# design.net
KiCad netlist of a schematic drawn in Altium Designer
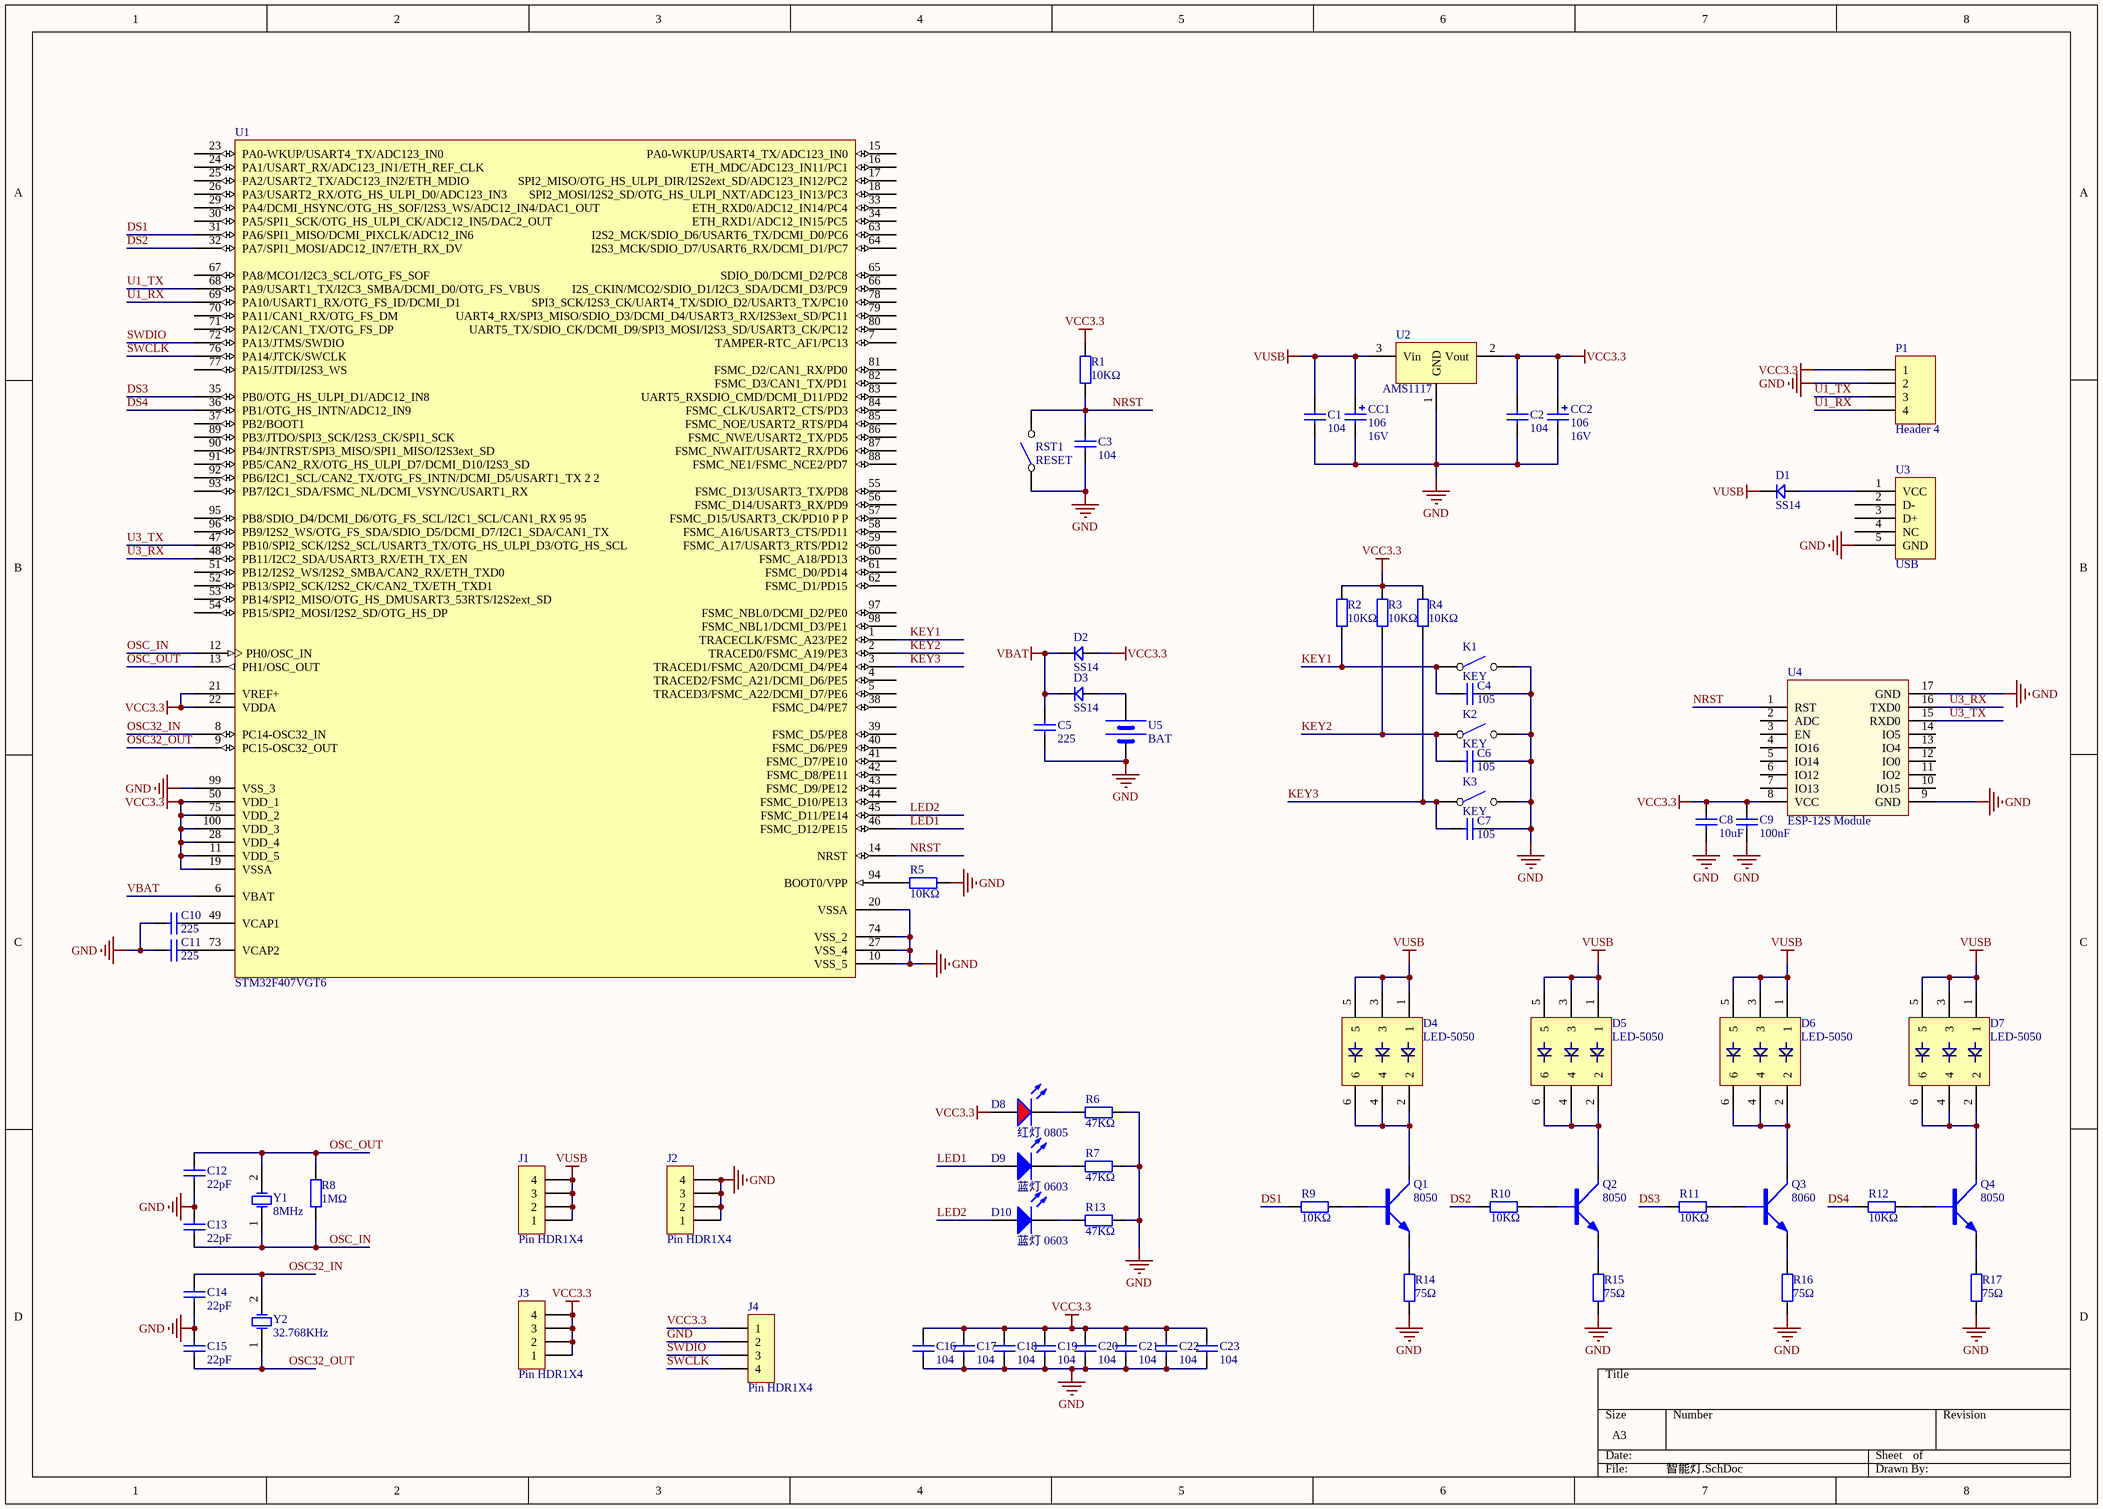
[diagram p0: 智能灯.SchDoc]

(export (version "E")
  (design (tool "Eeschema 10.0.6"))
  (components
    (comp (ref "C1")
      (value "104")
      (footprint "LC-0805_C")
      (description "贴片电容")
      (libsource (lib "Miscellaneous Devices LC") (part "0805 6.8nF (682) 10% 50V"))
    )
    (comp (ref "C2")
      (value "104")
      (footprint "LC-0805_C")
      (description "贴片电容")
      (libsource (lib "Miscellaneous Devices LC") (part "0805 6.8nF (682) 10% 50V"))
    )
    (comp (ref "C3")
      (value "104")
      (footprint "LC-0805_C")
      (description "贴片电容")
      (libsource (lib "Miscellaneous Devices LC") (part "0805 330nF (334) 10% 50V"))
    )
    (comp (ref "C4")
      (value "105")
      (footprint "LC-0805_C")
      (description "贴片电容")
      (libsource (lib "Miscellaneous Devices LC") (part "0805 6.8nF (682) 10% 50V"))
    )
    (comp (ref "C5")
      (value "225")
      (footprint "LC-0805_C")
      (description "贴片电容")
      (libsource (lib "Miscellaneous Devices LC") (part "0805 6.8nF (682) 10% 50V"))
    )
    (comp (ref "C6")
      (value "105")
      (footprint "LC-0805_C")
      (description "贴片电容")
      (libsource (lib "Miscellaneous Devices LC") (part "0805 6.8nF (682) 10% 50V"))
    )
    (comp (ref "C7")
      (value "105")
      (footprint "LC-0805_C")
      (description "贴片电容")
      (libsource (lib "Miscellaneous Devices LC") (part "0805 6.8nF (682) 10% 50V"))
    )
    (comp (ref "C8")
      (value "10uF")
      (footprint "LC-0805_C")
      (description "贴片电容")
      (libsource (lib "Miscellaneous Devices LC") (part "0805 6.8nF (682) 10% 50V"))
    )
    (comp (ref "C9")
      (value "100nF")
      (footprint "LC-0805_C")
      (description "贴片电容")
      (libsource (lib "Miscellaneous Devices LC") (part "0805 6.8nF (682) 10% 50V"))
    )
    (comp (ref "C10")
      (value "225")
      (footprint "LC-0805_C")
      (description "贴片电容")
      (libsource (lib "Miscellaneous Devices LC") (part "0805 6.8nF (682) 10% 50V"))
    )
    (comp (ref "C11")
      (value "225")
      (footprint "LC-0805_C")
      (description "贴片电容")
      (libsource (lib "Miscellaneous Devices LC") (part "0805 6.8nF (682) 10% 50V"))
    )
    (comp (ref "C12")
      (value "22pF")
      (footprint "LC-0805_C")
      (description "贴片电容")
      (libsource (lib "Miscellaneous Devices LC") (part "0805 6pF (6R0) 0.25pF 50V"))
    )
    (comp (ref "C13")
      (value "22pF")
      (footprint "LC-0805_C")
      (description "贴片电容")
      (libsource (lib "Miscellaneous Devices LC") (part "0805 6pF (6R0) 0.25pF 50V"))
    )
    (comp (ref "C14")
      (value "22pF")
      (footprint "LC-0805_C")
      (description "贴片电容")
      (libsource (lib "Miscellaneous Devices LC") (part "0805 6pF (6R0) 0.25pF 50V"))
    )
    (comp (ref "C15")
      (value "22pF")
      (footprint "LC-0805_C")
      (description "贴片电容")
      (libsource (lib "Miscellaneous Devices LC") (part "0805 6pF (6R0) 0.25pF 50V"))
    )
    (comp (ref "C16")
      (value "104")
      (footprint "LC-0805_C")
      (description "贴片电容")
      (libsource (lib "Miscellaneous Devices LC") (part "0805 6.8nF (682) 10% 50V"))
    )
    (comp (ref "C17")
      (value "104")
      (footprint "LC-0805_C")
      (description "贴片电容")
      (libsource (lib "Miscellaneous Devices LC") (part "0805 6.8nF (682) 10% 50V"))
    )
    (comp (ref "C18")
      (value "104")
      (footprint "LC-0805_C")
      (description "贴片电容")
      (libsource (lib "Miscellaneous Devices LC") (part "0805 6.8nF (682) 10% 50V"))
    )
    (comp (ref "C19")
      (value "104")
      (footprint "LC-0805_C")
      (description "贴片电容")
      (libsource (lib "Miscellaneous Devices LC") (part "0805 6.8nF (682) 10% 50V"))
    )
    (comp (ref "C20")
      (value "104")
      (footprint "LC-0805_C")
      (description "贴片电容")
      (libsource (lib "Miscellaneous Devices LC") (part "0805 6.8nF (682) 10% 50V"))
    )
    (comp (ref "C21")
      (value "104")
      (footprint "LC-0805_C")
      (description "贴片电容")
      (libsource (lib "Miscellaneous Devices LC") (part "0805 6.8nF (682) 10% 50V"))
    )
    (comp (ref "C22")
      (value "104")
      (footprint "LC-0805_C")
      (description "贴片电容")
      (libsource (lib "Miscellaneous Devices LC") (part "0805 6.8nF (682) 10% 50V"))
    )
    (comp (ref "C23")
      (value "104")
      (footprint "LC-0805_C")
      (description "贴片电容")
      (libsource (lib "Miscellaneous Devices LC") (part "0805 6.8nF (682) 10% 50V"))
    )
    (comp (ref "CC1")
      (value "Cap Tan C")
      (footprint "TAN-C-6032")
      (description "Polarized Capacitor (Radial)")
      (fields
        (field (name "CAPACITANCE") "106")
        (field (name "VOLTAGE") "16V")
        (field (name "PUBLISHER") "Altium Limited")
      )
      (libsource (lib "MyLib") (part "Cap Tan C"))
    )
    (comp (ref "CC2")
      (value "Cap Tan C")
      (footprint "TAN-C-6032")
      (description "Polarized Capacitor (Radial)")
      (fields
        (field (name "CAPACITANCE") "106")
        (field (name "VOLTAGE") "16V")
        (field (name "PUBLISHER") "Altium Limited")
      )
      (libsource (lib "MyLib") (part "Cap Tan C"))
    )
    (comp (ref "D1")
      (value "SS14")
      (footprint "Miscellaneous Devices LC:LC-SOD-123")
      (libsource (lib "Explorer STM32F407封装库") (part "D"))
    )
    (comp (ref "D2")
      (value "SS14")
      (footprint "Miscellaneous Devices LC:LC-SOD-123")
      (libsource (lib "Explorer STM32F407封装库") (part "D"))
    )
    (comp (ref "D3")
      (value "SS14")
      (footprint "Miscellaneous Devices LC:LC-SOD-123")
      (libsource (lib "Explorer STM32F407封装库") (part "D"))
    )
    (comp (ref "D4") (value "LED-5050") (footprint "LED-5050W") (libsource (lib "LED") (part "LED-5050")))
    (comp (ref "D5") (value "LED-5050") (footprint "LED-5050W") (libsource (lib "LED") (part "LED-5050")))
    (comp (ref "D6") (value "LED-5050") (footprint "LED-5050W") (libsource (lib "LED") (part "LED-5050")))
    (comp (ref "D7") (value "LED-5050") (footprint "LED-5050W") (libsource (lib "LED") (part "LED-5050")))
    (comp (ref "D8")
      (value "红灯 0805")
      (footprint "LC-0805_LED_S1")
      (description "发光二极管")
      (libsource (lib "Miscellaneous Devices LC") (part "0805 红灯"))
    )
    (comp (ref "D9")
      (value "蓝灯 0603")
      (footprint "Miscellaneous Devices LC:LC-0805_LED_S1")
      (description "发光二极管")
      (libsource (lib "Miscellaneous Devices LC") (part "0603 蓝灯"))
    )
    (comp (ref "D10")
      (value "蓝灯 0603")
      (footprint "Miscellaneous Devices LC:LC-0805_LED_S1")
      (description "发光二极管")
      (libsource (lib "Miscellaneous Devices LC") (part "0603 蓝灯"))
    )
    (comp (ref "J1")
      (value "Pin HDR1X4")
      (footprint "Pin HDR1X4/2.54mm-S")
      (libsource (lib "排针") (part "Pin HDR1X4"))
    )
    (comp (ref "J2")
      (value "Pin HDR1X4")
      (footprint "Pin HDR1X4/2.54mm-S")
      (libsource (lib "排针") (part "Pin HDR1X4"))
    )
    (comp (ref "J3")
      (value "Pin HDR1X4")
      (footprint "Pin HDR1X4/2.54mm-S")
      (libsource (lib "排针") (part "Pin HDR1X4"))
    )
    (comp (ref "J4")
      (value "Pin HDR1X4")
      (footprint "Pin HDR1X4/2.54mm-S")
      (libsource (lib "") (part "Pin HDR1X4_1"))
    )
    (comp (ref "K1")
      (value "KEY")
      (footprint "MyLib:KEY_2")
      (description "微动开关")
      (libsource (lib "MyLib") (part "KEY"))
    )
    (comp (ref "K2")
      (value "KEY")
      (footprint "MyLib:KEY_2")
      (description "微动开关")
      (libsource (lib "MyLib") (part "KEY"))
    )
    (comp (ref "K3")
      (value "KEY")
      (footprint "MyLib:KEY_2")
      (description "微动开关")
      (libsource (lib "MyLib") (part "KEY"))
    )
    (comp (ref "P1")
      (value "Header 4")
      (footprint "MyLib:HDR1X4")
      (description "Header, 4-Pin")
      (fields (field (name "PUBLISHER") "Altium Limited"))
      (libsource (lib "MyLib") (part "Header 4"))
    )
    (comp (ref "Q1")
      (value "8050")
      (footprint "SOT-23")
      (description "NPN三极管")
      (libsource (lib "三极管") (part "NPN"))
    )
    (comp (ref "Q2")
      (value "8050")
      (footprint "SOT-23")
      (description "NPN三极管")
      (libsource (lib "三极管") (part "NPN"))
    )
    (comp (ref "Q3")
      (value "8060")
      (footprint "SOT-23")
      (description "NPN三极管")
      (libsource (lib "三极管") (part "NPN"))
    )
    (comp (ref "Q4")
      (value "8050")
      (footprint "SOT-23")
      (description "NPN三极管")
      (libsource (lib "三极管") (part "NPN"))
    )
    (comp (ref "R1")
      (value "10KΩ")
      (footprint "LC-0805_R")
      (description "贴片电阻")
      (libsource (lib "Miscellaneous Devices LC") (part "0805 390KΩ (3903) 1%"))
    )
    (comp (ref "R2")
      (value "10KΩ")
      (footprint "LC-0805_R")
      (description "贴片电阻")
      (libsource (lib "") (part "0805 11KΩ (1102) 1%_1"))
    )
    (comp (ref "R3")
      (value "10KΩ")
      (footprint "LC-0805_R")
      (description "贴片电阻")
      (libsource (lib "") (part "0805 11KΩ (1102) 1%_1"))
    )
    (comp (ref "R4")
      (value "10KΩ")
      (footprint "LC-0805_R")
      (description "贴片电阻")
      (libsource (lib "") (part "0805 11KΩ (1102) 1%_1"))
    )
    (comp (ref "R5")
      (value "10KΩ")
      (footprint "LC-0805_R")
      (description "贴片电阻")
      (libsource (lib "Miscellaneous Devices LC") (part "0805 1.8KΩ (1801) 1%"))
    )
    (comp (ref "R6")
      (value "47KΩ")
      (footprint "LC-0805_R")
      (description "贴片电阻")
      (libsource (lib "Miscellaneous Devices LC") (part "0805 11KΩ (1102) 1%"))
    )
    (comp (ref "R7")
      (value "47KΩ")
      (footprint "LC-0805_R")
      (description "贴片电阻")
      (libsource (lib "Miscellaneous Devices LC") (part "0805 11KΩ (1102) 1%"))
    )
    (comp (ref "R8")
      (value "1MΩ")
      (footprint "LC-0805_R")
      (description "贴片电阻")
      (libsource (lib "Miscellaneous Devices LC") (part "0805 390KΩ (3903) 1%"))
    )
    (comp (ref "R9")
      (value "10KΩ")
      (footprint "LC-0805_R")
      (description "贴片电阻")
      (libsource (lib "") (part "0805 11KΩ (1102) 1%_2"))
    )
    (comp (ref "R10")
      (value "10KΩ")
      (footprint "电阻:0805R")
      (description "贴片电阻")
      (libsource (lib "") (part "0805 11KΩ (1102) 1%_2"))
    )
    (comp (ref "R11")
      (value "10KΩ")
      (footprint "电阻:0805R")
      (description "贴片电阻")
      (libsource (lib "") (part "0805 11KΩ (1102) 1%_2"))
    )
    (comp (ref "R12")
      (value "10KΩ")
      (footprint "电阻:0805R")
      (description "贴片电阻")
      (libsource (lib "") (part "0805 11KΩ (1102) 1%_2"))
    )
    (comp (ref "R13")
      (value "47KΩ")
      (footprint "LC-0805_R")
      (description "贴片电阻")
      (libsource (lib "Miscellaneous Devices LC") (part "0805 11KΩ (1102) 1%"))
    )
    (comp (ref "R14")
      (value "75Ω")
      (footprint "电阻:0805R")
      (description "贴片电阻")
      (libsource (lib "Miscellaneous Devices LC") (part "0805 1.2KΩ (1201) 1%"))
    )
    (comp (ref "R15")
      (value "75Ω")
      (footprint "电阻:0805R")
      (description "贴片电阻")
      (libsource (lib "Miscellaneous Devices LC") (part "0805 1.2KΩ (1201) 1%"))
    )
    (comp (ref "R16")
      (value "75Ω")
      (footprint "电阻:0805R")
      (description "贴片电阻")
      (libsource (lib "Miscellaneous Devices LC") (part "0805 1.2KΩ (1201) 1%"))
    )
    (comp (ref "R17")
      (value "75Ω")
      (footprint "电阻:0805R")
      (description "贴片电阻")
      (libsource (lib "Miscellaneous Devices LC") (part "0805 1.2KΩ (1201) 1%"))
    )
    (comp (ref "RST1")
      (value "RESET")
      (footprint "MyLib:KEY_2")
      (description "微动开关")
      (libsource (lib "MyLib") (part "KEY"))
    )
    (comp (ref "U1")
      (value "STM32F407VGT6")
      (footprint "STM32系列:LQFP100 14x14")
      (libsource (lib "STM32F407系列") (part "STM32F407VGT6"))
    )
    (comp (ref "U2")
      (value "AMS1117")
      (footprint "MyLib:SOT-223")
      (description "3.3V电压转换器AMS1117")
      (libsource (lib "My Footprint") (part "AMS1117"))
    )
    (comp (ref "U3") (value "USB") (footprint "MyLib:USB_B") (libsource (lib "MyLib") (part "USB")))
    (comp (ref "U4")
      (value "ESP-12S Module")
      (footprint "ESP-12S Module")
      (libsource (lib "MyLib") (part "ESP-12S Module"))
    )
    (comp (ref "U5")
      (value "BAT")
      (footprint "MyLib:CR1220_A")
      (description "纽扣电池座CR1220")
      (libsource (lib "MyLib") (part "BAT"))
    )
    (comp (ref "Y1")
      (value "8MHz")
      (footprint "MyLib:XTAL-SMD")
      (description "晶体振荡器")
      (fields (field (name "PUBLISHER") "Altium Limited"))
      (libsource (lib "MyLib") (part "XTAL"))
    )
    (comp (ref "Y2")
      (value "32.768KHz")
      (footprint "晶振:OSC-3x8-WI-B")
      (description "晶体振荡器")
      (fields (field (name "PUBLISHER") "Altium Limited"))
      (libsource (lib "MyLib") (part "XTAL"))
    )
  )
  (nets
    (net (code "1") (name "/DS1") (class "Default")
      (node (ref "R9") (pin "2") (pinfunction "2_2") (pintype "passive"))
      (node (ref "U1") (pin "31") (pinfunction "PA6/SPI1_MISO/DCMI_PIXCLK/ADC12_IN6_31") (pintype "bidirectional"))
    )
    (net (code "2") (name "/DS2") (class "Default")
      (node (ref "R10") (pin "2") (pinfunction "2_2") (pintype "passive"))
      (node (ref "U1") (pin "32") (pinfunction "PA7/SPI1_MOSI/ADC12_IN7/ETH_RX_DV_32") (pintype "bidirectional"))
    )
    (net (code "3") (name "/DS3") (class "Default")
      (node (ref "R11") (pin "2") (pinfunction "2_2") (pintype "passive"))
      (node (ref "U1") (pin "35") (pinfunction "PB0/OTG_HS_ULPI_D1/ADC12_IN8_35") (pintype "bidirectional"))
    )
    (net (code "4") (name "/DS4") (class "Default")
      (node (ref "R12") (pin "2") (pinfunction "2_2") (pintype "passive"))
      (node (ref "U1") (pin "36") (pinfunction "PB1/OTG_HS_INTN/ADC12_IN9_36") (pintype "bidirectional"))
    )
    (net (code "5") (name "/KEY1") (class "Default")
      (node (ref "C4") (pin "1") (pinfunction "1_1") (pintype "passive"))
      (node (ref "K1") (pin "1") (pinfunction "1_1") (pintype "passive"))
      (node (ref "R2") (pin "1") (pinfunction "1_1") (pintype "passive"))
      (node (ref "U1") (pin "1") (pinfunction "TRACECLK/FSMC_A23/PE2_1") (pintype "bidirectional"))
    )
    (net (code "6") (name "/KEY2") (class "Default")
      (node (ref "C6") (pin "1") (pinfunction "1_1") (pintype "passive"))
      (node (ref "K2") (pin "1") (pinfunction "1_1") (pintype "passive"))
      (node (ref "R3") (pin "1") (pinfunction "1_1") (pintype "passive"))
      (node (ref "U1") (pin "2") (pinfunction "TRACED0/FSMC_A19/PE3_2") (pintype "bidirectional"))
    )
    (net (code "7") (name "/KEY3") (class "Default")
      (node (ref "C7") (pin "1") (pinfunction "1_1") (pintype "passive"))
      (node (ref "K3") (pin "1") (pinfunction "1_1") (pintype "passive"))
      (node (ref "R4") (pin "1") (pinfunction "1_1") (pintype "passive"))
      (node (ref "U1") (pin "3") (pinfunction "TRACED1/FSMC_A20/DCMI_D4/PE4_3") (pintype "bidirectional"))
    )
    (net (code "8") (name "/LED1") (class "Default")
      (node (ref "D9") (pin "A") (pinfunction "A_A") (pintype "passive"))
      (node (ref "U1") (pin "46") (pinfunction "FSMC_D12/PE15_46") (pintype "bidirectional"))
    )
    (net (code "9") (name "/LED2") (class "Default")
      (node (ref "D10") (pin "A") (pinfunction "A_A") (pintype "passive"))
      (node (ref "U1") (pin "45") (pinfunction "FSMC_D11/PE14_45") (pintype "bidirectional"))
    )
    (net (code "10") (name "/NRST") (class "Default")
      (node (ref "C3") (pin "2") (pinfunction "2_2") (pintype "passive"))
      (node (ref "R1") (pin "1") (pinfunction "1_1") (pintype "passive"))
      (node (ref "RST1") (pin "2") (pinfunction "2_2") (pintype "passive"))
      (node (ref "U1") (pin "14") (pinfunction "NRST_14") (pintype "bidirectional"))
      (node (ref "U4") (pin "1") (pinfunction "RST_1") (pintype "passive"))
    )
    (net (code "11") (name "/OSC32_IN") (class "Default")
      (node (ref "C14") (pin "2") (pinfunction "2_2") (pintype "passive"))
      (node (ref "U1") (pin "8") (pinfunction "PC14-OSC32_IN_8") (pintype "bidirectional"))
      (node (ref "Y2") (pin "2") (pinfunction "OSC2_2") (pintype "passive"))
    )
    (net (code "12") (name "/OSC32_OUT") (class "Default")
      (node (ref "C15") (pin "1") (pinfunction "1_1") (pintype "passive"))
      (node (ref "U1") (pin "9") (pinfunction "PC15-OSC32_OUT_9") (pintype "bidirectional"))
      (node (ref "Y2") (pin "1") (pinfunction "OSC1_1") (pintype "passive"))
    )
    (net (code "13") (name "/OSC_IN") (class "Default")
      (node (ref "C13") (pin "1") (pinfunction "1_1") (pintype "passive"))
      (node (ref "R8") (pin "1") (pinfunction "1_1") (pintype "passive"))
      (node (ref "U1") (pin "12") (pinfunction "PH0/OSC_IN_12") (pintype "input"))
      (node (ref "Y1") (pin "1") (pinfunction "OSC1_1") (pintype "passive"))
    )
    (net (code "14") (name "/OSC_OUT") (class "Default")
      (node (ref "C12") (pin "2") (pinfunction "2_2") (pintype "passive"))
      (node (ref "R8") (pin "2") (pinfunction "2_2") (pintype "passive"))
      (node (ref "U1") (pin "13") (pinfunction "PH1/OSC_OUT_13") (pintype "output"))
      (node (ref "Y1") (pin "2") (pinfunction "OSC2_2") (pintype "passive"))
    )
    (net (code "15") (name "/SWCLK") (class "Default")
      (node (ref "J4") (pin "4") (pinfunction "4_4") (pintype "passive"))
      (node (ref "U1") (pin "76") (pinfunction "PA14/JTCK/SWCLK_76") (pintype "bidirectional"))
    )
    (net (code "16") (name "/SWDIO") (class "Default")
      (node (ref "J4") (pin "3") (pinfunction "3_3") (pintype "passive"))
      (node (ref "U1") (pin "72") (pinfunction "PA13/JTMS/SWDIO_72") (pintype "bidirectional"))
    )
    (net (code "17") (name "/U1_RX") (class "Default")
      (node (ref "P1") (pin "4") (pinfunction "4_4") (pintype "passive"))
      (node (ref "U1") (pin "69") (pinfunction "PA10/USART1_RX/OTG_FS_ID/DCMI_D1_69") (pintype "bidirectional"))
    )
    (net (code "18") (name "/U1_TX") (class "Default")
      (node (ref "P1") (pin "3") (pinfunction "3_3") (pintype "passive"))
      (node (ref "U1") (pin "68") (pinfunction "PA9/USART1_TX/I2C3_SMBA/DCMI_D0/OTG_FS_VBUS_68") (pintype "bidirectional"))
    )
    (net (code "19") (name "/U3_RX") (class "Default")
      (node (ref "U1") (pin "48") (pinfunction "PB11/I2C2_SDA/USART3_RX/ETH_TX_EN_48") (pintype "bidirectional"))
      (node (ref "U4") (pin "16") (pinfunction "TXD0_16") (pintype "passive"))
    )
    (net (code "20") (name "/U3_TX") (class "Default")
      (node (ref "U1") (pin "47") (pinfunction "PB10/SPI2_SCK/I2S2_SCL/USART3_TX/OTG_HS_ULPI_D3/OTG_HS_SCL_47") (pintype "bidirectional"))
      (node (ref "U4") (pin "15") (pinfunction "RXD0_15") (pintype "passive"))
    )
    (net (code "21") (name "GND") (class "Default")
      (node (ref "C1") (pin "1") (pinfunction "1_1") (pintype "passive"))
      (node (ref "C10") (pin "1") (pinfunction "1_1") (pintype "passive"))
      (node (ref "C11") (pin "1") (pinfunction "1_1") (pintype "passive"))
      (node (ref "C12") (pin "1") (pinfunction "1_1") (pintype "passive"))
      (node (ref "C13") (pin "2") (pinfunction "2_2") (pintype "passive"))
      (node (ref "C14") (pin "1") (pinfunction "1_1") (pintype "passive"))
      (node (ref "C15") (pin "2") (pinfunction "2_2") (pintype "passive"))
      (node (ref "C16") (pin "1") (pinfunction "1_1") (pintype "passive"))
      (node (ref "C17") (pin "1") (pinfunction "1_1") (pintype "passive"))
      (node (ref "C18") (pin "1") (pinfunction "1_1") (pintype "passive"))
      (node (ref "C19") (pin "1") (pinfunction "1_1") (pintype "passive"))
      (node (ref "C2") (pin "1") (pinfunction "1_1") (pintype "passive"))
      (node (ref "C20") (pin "1") (pinfunction "1_1") (pintype "passive"))
      (node (ref "C21") (pin "1") (pinfunction "1_1") (pintype "passive"))
      (node (ref "C22") (pin "1") (pinfunction "1_1") (pintype "passive"))
      (node (ref "C23") (pin "1") (pinfunction "1_1") (pintype "passive"))
      (node (ref "C3") (pin "1") (pinfunction "1_1") (pintype "passive"))
      (node (ref "C4") (pin "2") (pinfunction "2_2") (pintype "passive"))
      (node (ref "C5") (pin "1") (pinfunction "1_1") (pintype "passive"))
      (node (ref "C6") (pin "2") (pinfunction "2_2") (pintype "passive"))
      (node (ref "C7") (pin "2") (pinfunction "2_2") (pintype "passive"))
      (node (ref "C8") (pin "1") (pinfunction "1_1") (pintype "passive"))
      (node (ref "C9") (pin "1") (pinfunction "1_1") (pintype "passive"))
      (node (ref "CC1") (pin "1") (pinfunction "2_1") (pintype "passive"))
      (node (ref "CC2") (pin "1") (pinfunction "2_1") (pintype "passive"))
      (node (ref "J2") (pin "1") (pinfunction "1_1") (pintype "passive"))
      (node (ref "J2") (pin "2") (pinfunction "2_2") (pintype "passive"))
      (node (ref "J2") (pin "3") (pinfunction "3_3") (pintype "passive"))
      (node (ref "J2") (pin "4") (pinfunction "4_4") (pintype "passive"))
      (node (ref "J4") (pin "2") (pinfunction "2_2") (pintype "passive"))
      (node (ref "K1") (pin "2") (pinfunction "2_2") (pintype "passive"))
      (node (ref "K2") (pin "2") (pinfunction "2_2") (pintype "passive"))
      (node (ref "K3") (pin "2") (pinfunction "2_2") (pintype "passive"))
      (node (ref "P1") (pin "2") (pinfunction "2_2") (pintype "passive"))
      (node (ref "R13") (pin "2") (pinfunction "2_2") (pintype "passive"))
      (node (ref "R14") (pin "2") (pinfunction "2_2") (pintype "passive"))
      (node (ref "R15") (pin "2") (pinfunction "2_2") (pintype "passive"))
      (node (ref "R16") (pin "2") (pinfunction "2_2") (pintype "passive"))
      (node (ref "R17") (pin "2") (pinfunction "2_2") (pintype "passive"))
      (node (ref "R5") (pin "2") (pinfunction "2_2") (pintype "passive"))
      (node (ref "R6") (pin "2") (pinfunction "2_2") (pintype "passive"))
      (node (ref "R7") (pin "2") (pinfunction "2_2") (pintype "passive"))
      (node (ref "RST1") (pin "1") (pinfunction "1_1") (pintype "passive"))
      (node (ref "U1") (pin "10") (pinfunction "VSS_5_10") (pintype "power_in"))
      (node (ref "U1") (pin "20") (pinfunction "VSSA_20") (pintype "power_in"))
      (node (ref "U1") (pin "27") (pinfunction "VSS_4_27") (pintype "power_in"))
      (node (ref "U1") (pin "74") (pinfunction "VSS_2_74") (pintype "power_in"))
      (node (ref "U1") (pin "99") (pinfunction "VSS_3_99") (pintype "power_in"))
      (node (ref "U2") (pin "1") (pinfunction "GND_1") (pintype "passive"))
      (node (ref "U3") (pin "5") (pinfunction "GND_5") (pintype "passive"))
      (node (ref "U4") (pin "17") (pinfunction "GND_17") (pintype "passive"))
      (node (ref "U4") (pin "9") (pinfunction "GND_9") (pintype "passive"))
      (node (ref "U5") (pin "2") (pinfunction "GND_2") (pintype "passive"))
    )
    (net (code "22") (name "Net-(D4-Pad2)") (class "Default")
      (node (ref "D4") (pin "2") (pinfunction "2_2") (pintype "passive"))
      (node (ref "D4") (pin "4") (pinfunction "4_4") (pintype "passive"))
      (node (ref "D4") (pin "6") (pinfunction "6_6") (pintype "passive"))
      (node (ref "Q1") (pin "C") (pinfunction "C_C") (pintype "passive"))
    )
    (net (code "23") (name "Net-(D5-Pad2)") (class "Default")
      (node (ref "D5") (pin "2") (pinfunction "2_2") (pintype "passive"))
      (node (ref "D5") (pin "4") (pinfunction "4_4") (pintype "passive"))
      (node (ref "D5") (pin "6") (pinfunction "6_6") (pintype "passive"))
      (node (ref "Q2") (pin "C") (pinfunction "C_C") (pintype "passive"))
    )
    (net (code "24") (name "Net-(D6-Pad2)") (class "Default")
      (node (ref "D6") (pin "2") (pinfunction "2_2") (pintype "passive"))
      (node (ref "D6") (pin "4") (pinfunction "4_4") (pintype "passive"))
      (node (ref "D6") (pin "6") (pinfunction "6_6") (pintype "passive"))
      (node (ref "Q3") (pin "C") (pinfunction "C_C") (pintype "passive"))
    )
    (net (code "25") (name "Net-(D7-Pad2)") (class "Default")
      (node (ref "D7") (pin "2") (pinfunction "2_2") (pintype "passive"))
      (node (ref "D7") (pin "4") (pinfunction "4_4") (pintype "passive"))
      (node (ref "D7") (pin "6") (pinfunction "6_6") (pintype "passive"))
      (node (ref "Q4") (pin "C") (pinfunction "C_C") (pintype "passive"))
    )
    (net (code "26") (name "Net-(D8-PadK)") (class "Default")
      (node (ref "D8") (pin "K") (pinfunction "K_K") (pintype "passive"))
      (node (ref "R6") (pin "1") (pinfunction "1_1") (pintype "passive"))
    )
    (net (code "27") (name "Net-(D9-PadK)") (class "Default")
      (node (ref "D9") (pin "K") (pinfunction "K_K") (pintype "passive"))
      (node (ref "R7") (pin "1") (pinfunction "1_1") (pintype "passive"))
    )
    (net (code "28") (name "Net-(D10-PadK)") (class "Default")
      (node (ref "D10") (pin "K") (pinfunction "K_K") (pintype "passive"))
      (node (ref "R13") (pin "1") (pinfunction "1_1") (pintype "passive"))
    )
    (net (code "29") (name "Net-(Q1-PadB)") (class "Default")
      (node (ref "Q1") (pin "B") (pinfunction "B_B") (pintype "passive"))
      (node (ref "R9") (pin "1") (pinfunction "1_1") (pintype "passive"))
    )
    (net (code "30") (name "Net-(Q1-PadE)") (class "Default")
      (node (ref "Q1") (pin "E") (pinfunction "E_E") (pintype "passive"))
      (node (ref "R14") (pin "1") (pinfunction "1_1") (pintype "passive"))
    )
    (net (code "31") (name "Net-(Q2-PadB)") (class "Default")
      (node (ref "Q2") (pin "B") (pinfunction "B_B") (pintype "passive"))
      (node (ref "R10") (pin "1") (pinfunction "1_1") (pintype "passive"))
    )
    (net (code "32") (name "Net-(Q2-PadE)") (class "Default")
      (node (ref "Q2") (pin "E") (pinfunction "E_E") (pintype "passive"))
      (node (ref "R15") (pin "1") (pinfunction "1_1") (pintype "passive"))
    )
    (net (code "33") (name "Net-(Q3-PadB)") (class "Default")
      (node (ref "Q3") (pin "B") (pinfunction "B_B") (pintype "passive"))
      (node (ref "R11") (pin "1") (pinfunction "1_1") (pintype "passive"))
    )
    (net (code "34") (name "Net-(Q3-PadE)") (class "Default")
      (node (ref "Q3") (pin "E") (pinfunction "E_E") (pintype "passive"))
      (node (ref "R16") (pin "1") (pinfunction "1_1") (pintype "passive"))
    )
    (net (code "35") (name "Net-(Q4-PadB)") (class "Default")
      (node (ref "Q4") (pin "B") (pinfunction "B_B") (pintype "passive"))
      (node (ref "R12") (pin "1") (pinfunction "1_1") (pintype "passive"))
    )
    (net (code "36") (name "Net-(Q4-PadE)") (class "Default")
      (node (ref "Q4") (pin "E") (pinfunction "E_E") (pintype "passive"))
      (node (ref "R17") (pin "1") (pinfunction "1_1") (pintype "passive"))
    )
    (net (code "37") (name "Net-(U1-BOOT0{slash}VPP)") (class "Default")
      (node (ref "R5") (pin "1") (pinfunction "1_1") (pintype "passive"))
      (node (ref "U1") (pin "94") (pinfunction "BOOT0/VPP_94") (pintype "input"))
    )
    (net (code "38") (name "Net-(U1-VCAP1)") (class "Default")
      (node (ref "C10") (pin "2") (pinfunction "2_2") (pintype "passive"))
      (node (ref "U1") (pin "49") (pinfunction "VCAP1_49") (pintype "power_in"))
    )
    (net (code "39") (name "Net-(U1-VCAP2)") (class "Default")
      (node (ref "C11") (pin "2") (pinfunction "2_2") (pintype "passive"))
      (node (ref "U1") (pin "73") (pinfunction "VCAP2_73") (pintype "passive"))
    )
    (net (code "40") (name "Net-(U3-VCC)") (class "Default")
      (node (ref "D1") (pin "1") (pintype "passive"))
      (node (ref "U3") (pin "1") (pinfunction "VCC_1") (pintype "passive"))
    )
    (net (code "41") (name "Net-(U5-VCC)") (class "Default")
      (node (ref "D3") (pin "1") (pintype "passive"))
      (node (ref "U5") (pin "1") (pinfunction "VCC_1") (pintype "passive"))
    )
    (net (code "42") (name "VBAT") (class "Default")
      (node (ref "C5") (pin "2") (pinfunction "2_2") (pintype "passive"))
      (node (ref "D2") (pin "2") (pintype "passive"))
      (node (ref "D3") (pin "2") (pintype "passive"))
      (node (ref "U1") (pin "6") (pinfunction "VBAT_6") (pintype "power_in"))
    )
    (net (code "43") (name "VCC3.3") (class "Default")
      (node (ref "C16") (pin "2") (pinfunction "2_2") (pintype "passive"))
      (node (ref "C17") (pin "2") (pinfunction "2_2") (pintype "passive"))
      (node (ref "C18") (pin "2") (pinfunction "2_2") (pintype "passive"))
      (node (ref "C19") (pin "2") (pinfunction "2_2") (pintype "passive"))
      (node (ref "C2") (pin "2") (pinfunction "2_2") (pintype "passive"))
      (node (ref "C20") (pin "2") (pinfunction "2_2") (pintype "passive"))
      (node (ref "C21") (pin "2") (pinfunction "2_2") (pintype "passive"))
      (node (ref "C22") (pin "2") (pinfunction "2_2") (pintype "passive"))
      (node (ref "C23") (pin "2") (pinfunction "2_2") (pintype "passive"))
      (node (ref "C8") (pin "2") (pinfunction "2_2") (pintype "passive"))
      (node (ref "C9") (pin "2") (pinfunction "2_2") (pintype "passive"))
      (node (ref "CC2") (pin "2") (pinfunction "1_2") (pintype "passive"))
      (node (ref "D2") (pin "1") (pintype "passive"))
      (node (ref "D8") (pin "A") (pinfunction "A_A") (pintype "passive"))
      (node (ref "J3") (pin "1") (pinfunction "1_1") (pintype "passive"))
      (node (ref "J3") (pin "2") (pinfunction "2_2") (pintype "passive"))
      (node (ref "J3") (pin "3") (pinfunction "3_3") (pintype "passive"))
      (node (ref "J3") (pin "4") (pinfunction "4_4") (pintype "passive"))
      (node (ref "J4") (pin "1") (pinfunction "1_1") (pintype "passive"))
      (node (ref "P1") (pin "1") (pinfunction "1_1") (pintype "passive"))
      (node (ref "R1") (pin "2") (pinfunction "2_2") (pintype "passive"))
      (node (ref "R2") (pin "2") (pinfunction "2_2") (pintype "passive"))
      (node (ref "R3") (pin "2") (pinfunction "2_2") (pintype "passive"))
      (node (ref "R4") (pin "2") (pinfunction "2_2") (pintype "passive"))
      (node (ref "U1") (pin "100") (pinfunction "VDD_3_100") (pintype "power_in"))
      (node (ref "U1") (pin "11") (pinfunction "VDD_5_11") (pintype "power_in"))
      (node (ref "U1") (pin "19") (pinfunction "VSSA_19") (pintype "power_in"))
      (node (ref "U1") (pin "21") (pinfunction "VREF+_21") (pintype "power_in"))
      (node (ref "U1") (pin "22") (pinfunction "VDDA_22") (pintype "power_in"))
      (node (ref "U1") (pin "28") (pinfunction "VDD_4_28") (pintype "power_in"))
      (node (ref "U1") (pin "50") (pinfunction "VDD_1_50") (pintype "power_in"))
      (node (ref "U1") (pin "75") (pinfunction "VDD_2_75") (pintype "power_in"))
      (node (ref "U2") (pin "2") (pinfunction "Vout_2") (pintype "passive"))
      (node (ref "U4") (pin "8") (pinfunction "VCC_8") (pintype "passive"))
    )
    (net (code "44") (name "VUSB") (class "Default")
      (node (ref "C1") (pin "2") (pinfunction "2_2") (pintype "passive"))
      (node (ref "CC1") (pin "2") (pinfunction "1_2") (pintype "passive"))
      (node (ref "D1") (pin "2") (pintype "passive"))
      (node (ref "D4") (pin "1") (pinfunction "1_1") (pintype "passive"))
      (node (ref "D4") (pin "3") (pinfunction "3_3") (pintype "passive"))
      (node (ref "D4") (pin "5") (pinfunction "5_5") (pintype "passive"))
      (node (ref "D5") (pin "1") (pinfunction "1_1") (pintype "passive"))
      (node (ref "D5") (pin "3") (pinfunction "3_3") (pintype "passive"))
      (node (ref "D5") (pin "5") (pinfunction "5_5") (pintype "passive"))
      (node (ref "D6") (pin "1") (pinfunction "1_1") (pintype "passive"))
      (node (ref "D6") (pin "3") (pinfunction "3_3") (pintype "passive"))
      (node (ref "D6") (pin "5") (pinfunction "5_5") (pintype "passive"))
      (node (ref "D7") (pin "1") (pinfunction "1_1") (pintype "passive"))
      (node (ref "D7") (pin "3") (pinfunction "3_3") (pintype "passive"))
      (node (ref "D7") (pin "5") (pinfunction "5_5") (pintype "passive"))
      (node (ref "J1") (pin "1") (pinfunction "1_1") (pintype "passive"))
      (node (ref "J1") (pin "2") (pinfunction "2_2") (pintype "passive"))
      (node (ref "J1") (pin "3") (pinfunction "3_3") (pintype "passive"))
      (node (ref "J1") (pin "4") (pinfunction "4_4") (pintype "passive"))
      (node (ref "U2") (pin "3") (pinfunction "Vin_3") (pintype "passive"))
    )
    (net (code "45") (name "unconnected-(U1-ETH_MDC{slash}ADC123_IN11{slash}PC1-Pad16)") (class "Default")
      (node (ref "U1") (pin "16") (pinfunction "ETH_MDC/ADC123_IN11/PC1_16") (pintype "bidirectional"))
    )
    (net (code "46") (name "unconnected-(U1-ETH_RXD0{slash}ADC12_IN14{slash}PC4-Pad33)") (class "Default")
      (node (ref "U1") (pin "33") (pinfunction "ETH_RXD0/ADC12_IN14/PC4_33") (pintype "bidirectional"))
    )
    (net (code "47") (name "unconnected-(U1-ETH_RXD1{slash}ADC12_IN15{slash}PC5-Pad34)") (class "Default")
      (node (ref "U1") (pin "34") (pinfunction "ETH_RXD1/ADC12_IN15/PC5_34") (pintype "bidirectional"))
    )
    (net (code "48") (name "unconnected-(U1-FSMC_A16{slash}USART3_CTS{slash}PD11-Pad58)") (class "Default")
      (node (ref "U1") (pin "58") (pinfunction "FSMC_A16/USART3_CTS/PD11_58") (pintype "bidirectional"))
    )
    (net (code "49") (name "unconnected-(U1-FSMC_A17{slash}USART3_RTS{slash}PD12-Pad59)") (class "Default")
      (node (ref "U1") (pin "59") (pinfunction "FSMC_A17/USART3_RTS/PD12_59") (pintype "bidirectional"))
    )
    (net (code "50") (name "unconnected-(U1-FSMC_A18{slash}PD13-Pad60)") (class "Default")
      (node (ref "U1") (pin "60") (pinfunction "FSMC_A18/PD13_60") (pintype "bidirectional"))
    )
    (net (code "51") (name "unconnected-(U1-FSMC_CLK{slash}USART2_CTS{slash}PD3-Pad84)") (class "Default")
      (node (ref "U1") (pin "84") (pinfunction "FSMC_CLK/USART2_CTS/PD3_84") (pintype "bidirectional"))
    )
    (net (code "52") (name "unconnected-(U1-FSMC_D0{slash}PD14-Pad61)") (class "Default")
      (node (ref "U1") (pin "61") (pinfunction "FSMC_D0/PD14_61") (pintype "bidirectional"))
    )
    (net (code "53") (name "unconnected-(U1-FSMC_D1{slash}PD15-Pad62)") (class "Default")
      (node (ref "U1") (pin "62") (pinfunction "FSMC_D1/PD15_62") (pintype "bidirectional"))
    )
    (net (code "54") (name "unconnected-(U1-FSMC_D2{slash}CAN1_RX{slash}PD0-Pad81)") (class "Default")
      (node (ref "U1") (pin "81") (pinfunction "FSMC_D2/CAN1_RX/PD0_81") (pintype "bidirectional"))
    )
    (net (code "55") (name "unconnected-(U1-FSMC_D3{slash}CAN1_TX{slash}PD1-Pad82)") (class "Default")
      (node (ref "U1") (pin "82") (pinfunction "FSMC_D3/CAN1_TX/PD1_82") (pintype "bidirectional"))
    )
    (net (code "56") (name "unconnected-(U1-FSMC_D4{slash}PE7-Pad38)") (class "Default")
      (node (ref "U1") (pin "38") (pinfunction "FSMC_D4/PE7_38") (pintype "bidirectional"))
    )
    (net (code "57") (name "unconnected-(U1-FSMC_D5{slash}PE8-Pad39)") (class "Default")
      (node (ref "U1") (pin "39") (pinfunction "FSMC_D5/PE8_39") (pintype "bidirectional"))
    )
    (net (code "58") (name "unconnected-(U1-FSMC_D6{slash}PE9-Pad40)") (class "Default")
      (node (ref "U1") (pin "40") (pinfunction "FSMC_D6/PE9_40") (pintype "bidirectional"))
    )
    (net (code "59") (name "unconnected-(U1-FSMC_D7{slash}PE10-Pad41)") (class "Default")
      (node (ref "U1") (pin "41") (pinfunction "FSMC_D7/PE10_41") (pintype "bidirectional"))
    )
    (net (code "60") (name "unconnected-(U1-FSMC_D8{slash}PE11-Pad42)") (class "Default")
      (node (ref "U1") (pin "42") (pinfunction "FSMC_D8/PE11_42") (pintype "bidirectional"))
    )
    (net (code "61") (name "unconnected-(U1-FSMC_D9{slash}PE12-Pad43)") (class "Default")
      (node (ref "U1") (pin "43") (pinfunction "FSMC_D9/PE12_43") (pintype "bidirectional"))
    )
    (net (code "62") (name "unconnected-(U1-FSMC_D10{slash}PE13-Pad44)") (class "Default")
      (node (ref "U1") (pin "44") (pinfunction "FSMC_D10/PE13_44") (pintype "bidirectional"))
    )
    (net (code "63") (name "unconnected-(U1-FSMC_D13{slash}USART3_TX{slash}PD8-Pad55)") (class "Default")
      (node (ref "U1") (pin "55") (pinfunction "FSMC_D13/USART3_TX/PD8_55") (pintype "bidirectional"))
    )
    (net (code "64") (name "unconnected-(U1-FSMC_D14{slash}USART3_RX{slash}PD9-Pad56)") (class "Default")
      (node (ref "U1") (pin "56") (pinfunction "FSMC_D14/USART3_RX/PD9_56") (pintype "bidirectional"))
    )
    (net (code "65") (name "unconnected-(U1-FSMC_D15{slash}USART3_CK{slash}PD10_P_P-Pad57)") (class "Default")
      (node (ref "U1") (pin "57") (pinfunction "FSMC_D15/USART3_CK/PD10_P_P_57") (pintype "bidirectional"))
    )
    (net (code "66") (name "unconnected-(U1-FSMC_NBL0{slash}DCMI_D2{slash}PE0-Pad97)") (class "Default")
      (node (ref "U1") (pin "97") (pinfunction "FSMC_NBL0/DCMI_D2/PE0_97") (pintype "bidirectional"))
    )
    (net (code "67") (name "unconnected-(U1-FSMC_NBL1{slash}DCMI_D3{slash}PE1-Pad98)") (class "Default")
      (node (ref "U1") (pin "98") (pinfunction "FSMC_NBL1/DCMI_D3/PE1_98") (pintype "bidirectional"))
    )
    (net (code "68") (name "unconnected-(U1-FSMC_NE1{slash}FSMC_NCE2{slash}PD7-Pad88)") (class "Default")
      (node (ref "U1") (pin "88") (pinfunction "FSMC_NE1/FSMC_NCE2/PD7_88") (pintype "bidirectional"))
    )
    (net (code "69") (name "unconnected-(U1-FSMC_NOE{slash}USART2_RTS{slash}PD4-Pad85)") (class "Default")
      (node (ref "U1") (pin "85") (pinfunction "FSMC_NOE/USART2_RTS/PD4_85") (pintype "bidirectional"))
    )
    (net (code "70") (name "unconnected-(U1-FSMC_NWAIT{slash}USART2_RX{slash}PD6-Pad87)") (class "Default")
      (node (ref "U1") (pin "87") (pinfunction "FSMC_NWAIT/USART2_RX/PD6_87") (pintype "bidirectional"))
    )
    (net (code "71") (name "unconnected-(U1-FSMC_NWE{slash}USART2_TX{slash}PD5-Pad86)") (class "Default")
      (node (ref "U1") (pin "86") (pinfunction "FSMC_NWE/USART2_TX/PD5_86") (pintype "bidirectional"))
    )
    (net (code "72") (name "unconnected-(U1-I2S2_MCK{slash}SDIO_D6{slash}USART6_TX{slash}DCMI_D0{slash}PC6-Pad63)") (class "Default")
      (node (ref "U1") (pin "63") (pinfunction "I2S2_MCK/SDIO_D6/USART6_TX/DCMI_D0/PC6_63") (pintype "bidirectional"))
    )
    (net (code "73") (name "unconnected-(U1-I2S3_MCK{slash}SDIO_D7{slash}USART6_RX{slash}DCMI_D1{slash}PC7-Pad64)") (class "Default")
      (node (ref "U1") (pin "64") (pinfunction "I2S3_MCK/SDIO_D7/USART6_RX/DCMI_D1/PC7_64") (pintype "bidirectional"))
    )
    (net (code "74") (name "unconnected-(U1-I2S_CKIN{slash}MCO2{slash}SDIO_D1{slash}I2C3_SDA{slash}DCMI_D3{slash}PC9-Pad66)") (class "Default")
      (node (ref "U1") (pin "66") (pinfunction "I2S_CKIN/MCO2/SDIO_D1/I2C3_SDA/DCMI_D3/PC9_66") (pintype "bidirectional"))
    )
    (net (code "75") (name "unconnected-(U1-PA0-WKUP{slash}USART4_TX{slash}ADC123_IN0-Pad15)") (class "Default")
      (node (ref "U1") (pin "15") (pinfunction "PA0-WKUP/USART4_TX/ADC123_IN0_15") (pintype "bidirectional"))
    )
    (net (code "76") (name "unconnected-(U1-PA0-WKUP{slash}USART4_TX{slash}ADC123_IN0-Pad23)") (class "Default")
      (node (ref "U1") (pin "23") (pinfunction "PA0-WKUP/USART4_TX/ADC123_IN0_23") (pintype "bidirectional"))
    )
    (net (code "77") (name "unconnected-(U1-PA1{slash}USART_RX{slash}ADC123_IN1{slash}ETH_REF_CLK-Pad24)") (class "Default")
      (node (ref "U1") (pin "24") (pinfunction "PA1/USART_RX/ADC123_IN1/ETH_REF_CLK_24") (pintype "bidirectional"))
    )
    (net (code "78") (name "unconnected-(U1-PA2{slash}USART2_TX{slash}ADC123_IN2{slash}ETH_MDIO-Pad25)") (class "Default")
      (node (ref "U1") (pin "25") (pinfunction "PA2/USART2_TX/ADC123_IN2/ETH_MDIO_25") (pintype "bidirectional"))
    )
    (net (code "79") (name "unconnected-(U1-PA3{slash}USART2_RX{slash}OTG_HS_ULPI_D0{slash}ADC123_IN3-Pad26)") (class "Default")
      (node (ref "U1") (pin "26") (pinfunction "PA3/USART2_RX/OTG_HS_ULPI_D0/ADC123_IN3_26") (pintype "bidirectional"))
    )
    (net (code "80") (name "unconnected-(U1-PA4{slash}DCMI_HSYNC{slash}OTG_HS_SOF{slash}I2S3_WS{slash}ADC12_IN4{slash}DAC1_OUT-Pad29)") (class "Default")
      (node (ref "U1") (pin "29") (pinfunction "PA4/DCMI_HSYNC/OTG_HS_SOF/I2S3_WS/ADC12_IN4/DAC1_OUT_29") (pintype "bidirectional"))
    )
    (net (code "81") (name "unconnected-(U1-PA5{slash}SPI1_SCK{slash}OTG_HS_ULPI_CK{slash}ADC12_IN5{slash}DAC2_OUT-Pad30)") (class "Default")
      (node (ref "U1") (pin "30") (pinfunction "PA5/SPI1_SCK/OTG_HS_ULPI_CK/ADC12_IN5/DAC2_OUT_30") (pintype "bidirectional"))
    )
    (net (code "82") (name "unconnected-(U1-PA8{slash}MCO1{slash}I2C3_SCL{slash}OTG_FS_SOF-Pad67)") (class "Default")
      (node (ref "U1") (pin "67") (pinfunction "PA8/MCO1/I2C3_SCL/OTG_FS_SOF_67") (pintype "bidirectional"))
    )
    (net (code "83") (name "unconnected-(U1-PA11{slash}CAN1_RX{slash}OTG_FS_DM-Pad70)") (class "Default")
      (node (ref "U1") (pin "70") (pinfunction "PA11/CAN1_RX/OTG_FS_DM_70") (pintype "bidirectional"))
    )
    (net (code "84") (name "unconnected-(U1-PA12{slash}CAN1_TX{slash}OTG_FS_DP-Pad71)") (class "Default")
      (node (ref "U1") (pin "71") (pinfunction "PA12/CAN1_TX/OTG_FS_DP_71") (pintype "bidirectional"))
    )
    (net (code "85") (name "unconnected-(U1-PA15{slash}JTDI{slash}I2S3_WS-Pad77)") (class "Default")
      (node (ref "U1") (pin "77") (pinfunction "PA15/JTDI/I2S3_WS_77") (pintype "bidirectional"))
    )
    (net (code "86") (name "unconnected-(U1-PB2{slash}BOOT1-Pad37)") (class "Default")
      (node (ref "U1") (pin "37") (pinfunction "PB2/BOOT1_37") (pintype "bidirectional"))
    )
    (net (code "87") (name "unconnected-(U1-PB3{slash}JTDO{slash}SPI3_SCK{slash}I2S3_CK{slash}SPI1_SCK-Pad89)") (class "Default")
      (node (ref "U1") (pin "89") (pinfunction "PB3/JTDO/SPI3_SCK/I2S3_CK/SPI1_SCK_89") (pintype "bidirectional"))
    )
    (net (code "88") (name "unconnected-(U1-PB4{slash}JNTRST{slash}SPI3_MISO{slash}SPI1_MISO{slash}I2S3ext_SD-Pad90)") (class "Default")
      (node (ref "U1") (pin "90") (pinfunction "PB4/JNTRST/SPI3_MISO/SPI1_MISO/I2S3ext_SD_90") (pintype "bidirectional"))
    )
    (net (code "89") (name "unconnected-(U1-PB5{slash}CAN2_RX{slash}OTG_HS_ULPI_D7{slash}DCMI_D10{slash}I2S3_SD-Pad91)") (class "Default")
      (node (ref "U1") (pin "91") (pinfunction "PB5/CAN2_RX/OTG_HS_ULPI_D7/DCMI_D10/I2S3_SD_91") (pintype "bidirectional"))
    )
    (net (code "90") (name "unconnected-(U1-PB6{slash}I2C1_SCL{slash}CAN2_TX{slash}OTG_FS_INTN{slash}DCMI_D5{slash}USART1_TX_2_2-Pad92)") (class "Default")
      (node (ref "U1") (pin "92") (pinfunction "PB6/I2C1_SCL/CAN2_TX/OTG_FS_INTN/DCMI_D5/USART1_TX_2_2_92") (pintype "bidirectional"))
    )
    (net (code "91") (name "unconnected-(U1-PB7{slash}I2C1_SDA{slash}FSMC_NL{slash}DCMI_VSYNC{slash}USART1_RX-Pad93)") (class "Default")
      (node (ref "U1") (pin "93") (pinfunction "PB7/I2C1_SDA/FSMC_NL/DCMI_VSYNC/USART1_RX_93") (pintype "bidirectional"))
    )
    (net (code "92") (name "unconnected-(U1-PB8{slash}SDIO_D4{slash}DCMI_D6{slash}OTG_FS_SCL{slash}I2C1_SCL{slash}CAN1_RX_95_95-Pad95)") (class "Default")
      (node (ref "U1") (pin "95") (pinfunction "PB8/SDIO_D4/DCMI_D6/OTG_FS_SCL/I2C1_SCL/CAN1_RX_95_95_95") (pintype "bidirectional"))
    )
    (net (code "93") (name "unconnected-(U1-PB9{slash}I2S2_WS{slash}OTG_FS_SDA{slash}SDIO_D5{slash}DCMI_D7{slash}I2C1_SDA{slash}CAN1_TX-Pad96)") (class "Default")
      (node (ref "U1") (pin "96") (pinfunction "PB9/I2S2_WS/OTG_FS_SDA/SDIO_D5/DCMI_D7/I2C1_SDA/CAN1_TX_96") (pintype "bidirectional"))
    )
    (net (code "94") (name "unconnected-(U1-PB12{slash}I2S2_WS{slash}I2S2_SMBA{slash}CAN2_RX{slash}ETH_TXD0-Pad51)") (class "Default")
      (node (ref "U1") (pin "51") (pinfunction "PB12/I2S2_WS/I2S2_SMBA/CAN2_RX/ETH_TXD0_51") (pintype "bidirectional"))
    )
    (net (code "95") (name "unconnected-(U1-PB13{slash}SPI2_SCK{slash}I2S2_CK{slash}CAN2_TX{slash}ETH_TXD1-Pad52)") (class "Default")
      (node (ref "U1") (pin "52") (pinfunction "PB13/SPI2_SCK/I2S2_CK/CAN2_TX/ETH_TXD1_52") (pintype "bidirectional"))
    )
    (net (code "96") (name "unconnected-(U1-PB14{slash}SPI2_MISO{slash}OTG_HS_DMUSART3_53RTS{slash}I2S2ext_SD-Pad53)") (class "Default")
      (node (ref "U1") (pin "53") (pinfunction "PB14/SPI2_MISO/OTG_HS_DMUSART3_53RTS/I2S2ext_SD_53") (pintype "bidirectional"))
    )
    (net (code "97") (name "unconnected-(U1-PB15{slash}SPI2_MOSI{slash}I2S2_SD{slash}OTG_HS_DP-Pad54)") (class "Default")
      (node (ref "U1") (pin "54") (pinfunction "PB15/SPI2_MOSI/I2S2_SD/OTG_HS_DP_54") (pintype "bidirectional"))
    )
    (net (code "98") (name "unconnected-(U1-SDIO_D0{slash}DCMI_D2{slash}PC8-Pad65)") (class "Default")
      (node (ref "U1") (pin "65") (pinfunction "SDIO_D0/DCMI_D2/PC8_65") (pintype "bidirectional"))
    )
    (net (code "99") (name "unconnected-(U1-SPI2_MISO{slash}OTG_HS_ULPI_DIR{slash}I2S2ext_SD{slash}ADC123_IN12{slash}PC2-Pad17)") (class "Default")
      (node (ref "U1") (pin "17") (pinfunction "SPI2_MISO/OTG_HS_ULPI_DIR/I2S2ext_SD/ADC123_IN12/PC2_17") (pintype "bidirectional"))
    )
    (net (code "100") (name "unconnected-(U1-SPI2_MOSI{slash}I2S2_SD{slash}OTG_HS_ULPI_NXT{slash}ADC123_IN13{slash}PC3-Pad18)") (class "Default")
      (node (ref "U1") (pin "18") (pinfunction "SPI2_MOSI/I2S2_SD/OTG_HS_ULPI_NXT/ADC123_IN13/PC3_18") (pintype "bidirectional"))
    )
    (net (code "101") (name "unconnected-(U1-SPI3_SCK{slash}I2S3_CK{slash}UART4_TX{slash}SDIO_D2{slash}USART3_TX{slash}PC10-Pad78)") (class "Default")
      (node (ref "U1") (pin "78") (pinfunction "SPI3_SCK/I2S3_CK/UART4_TX/SDIO_D2/USART3_TX/PC10_78") (pintype "bidirectional"))
    )
    (net (code "102") (name "unconnected-(U1-TAMPER-RTC_AF1{slash}PC13-Pad7)") (class "Default")
      (node (ref "U1") (pin "7") (pinfunction "TAMPER-RTC_AF1/PC13_7") (pintype "bidirectional"))
    )
    (net (code "103") (name "unconnected-(U1-TRACED2{slash}FSMC_A21{slash}DCMI_D6{slash}PE5-Pad4)") (class "Default")
      (node (ref "U1") (pin "4") (pinfunction "TRACED2/FSMC_A21/DCMI_D6/PE5_4") (pintype "bidirectional"))
    )
    (net (code "104") (name "unconnected-(U1-TRACED3{slash}FSMC_A22{slash}DCMI_D7{slash}PE6-Pad5)") (class "Default")
      (node (ref "U1") (pin "5") (pinfunction "TRACED3/FSMC_A22/DCMI_D7/PE6_5") (pintype "bidirectional"))
    )
    (net (code "105") (name "unconnected-(U1-UART4_RX{slash}SPI3_MISO{slash}SDIO_D3{slash}DCMI_D4{slash}USART3_RX{slash}I2S3ext_SD{slash}PC11-Pad79)") (class "Default")
      (node (ref "U1") (pin "79") (pinfunction "UART4_RX/SPI3_MISO/SDIO_D3/DCMI_D4/USART3_RX/I2S3ext_SD/PC11_79") (pintype "bidirectional"))
    )
    (net (code "106") (name "unconnected-(U1-UART5_RXSDIO_CMD{slash}DCMI_D11{slash}PD2-Pad83)") (class "Default")
      (node (ref "U1") (pin "83") (pinfunction "UART5_RXSDIO_CMD/DCMI_D11/PD2_83") (pintype "bidirectional"))
    )
    (net (code "107") (name "unconnected-(U1-UART5_TX{slash}SDIO_CK{slash}DCMI_D9{slash}SPI3_MOSI{slash}I2S3_SD{slash}USART3_CK{slash}PC12-Pad80)") (class "Default")
      (node (ref "U1") (pin "80") (pinfunction "UART5_TX/SDIO_CK/DCMI_D9/SPI3_MOSI/I2S3_SD/USART3_CK/PC12_80") (pintype "bidirectional"))
    )
    (net (code "108") (name "unconnected-(U3-D+-Pad3)") (class "Default")
      (node (ref "U3") (pin "3") (pinfunction "D+_3") (pintype "passive"))
    )
    (net (code "109") (name "unconnected-(U3-D--Pad2)") (class "Default")
      (node (ref "U3") (pin "2") (pinfunction "D-_2") (pintype "passive"))
    )
    (net (code "110") (name "unconnected-(U3-NC-Pad4)") (class "Default")
      (node (ref "U3") (pin "4") (pinfunction "NC_4") (pintype "passive"))
    )
    (net (code "111") (name "unconnected-(U4-ADC-Pad2)") (class "Default")
      (node (ref "U4") (pin "2") (pinfunction "ADC_2") (pintype "passive"))
    )
    (net (code "112") (name "unconnected-(U4-EN-Pad3)") (class "Default")
      (node (ref "U4") (pin "3") (pinfunction "EN_3") (pintype "passive"))
    )
    (net (code "113") (name "unconnected-(U4-IO0-Pad12)") (class "Default")
      (node (ref "U4") (pin "12") (pinfunction "IO0_12") (pintype "passive"))
    )
    (net (code "114") (name "unconnected-(U4-IO2-Pad11)") (class "Default")
      (node (ref "U4") (pin "11") (pinfunction "IO2_11") (pintype "passive"))
    )
    (net (code "115") (name "unconnected-(U4-IO4-Pad13)") (class "Default")
      (node (ref "U4") (pin "13") (pinfunction "IO4_13") (pintype "passive"))
    )
    (net (code "116") (name "unconnected-(U4-IO5-Pad14)") (class "Default")
      (node (ref "U4") (pin "14") (pinfunction "IO5_14") (pintype "passive"))
    )
    (net (code "117") (name "unconnected-(U4-IO12-Pad6)") (class "Default")
      (node (ref "U4") (pin "6") (pinfunction "IO12_6") (pintype "passive"))
    )
    (net (code "118") (name "unconnected-(U4-IO13-Pad7)") (class "Default")
      (node (ref "U4") (pin "7") (pinfunction "IO13_7") (pintype "passive"))
    )
    (net (code "119") (name "unconnected-(U4-IO14-Pad5)") (class "Default")
      (node (ref "U4") (pin "5") (pinfunction "IO14_5") (pintype "passive"))
    )
    (net (code "120") (name "unconnected-(U4-IO15-Pad10)") (class "Default")
      (node (ref "U4") (pin "10") (pinfunction "IO15_10") (pintype "passive"))
    )
    (net (code "121") (name "unconnected-(U4-IO16-Pad4)") (class "Default")
      (node (ref "U4") (pin "4") (pinfunction "IO16_4") (pintype "passive"))
    )
  )
)
